# MyProject_2025-03-29.net
KiCad netlist of a schematic drawn in EasyEDA Pro
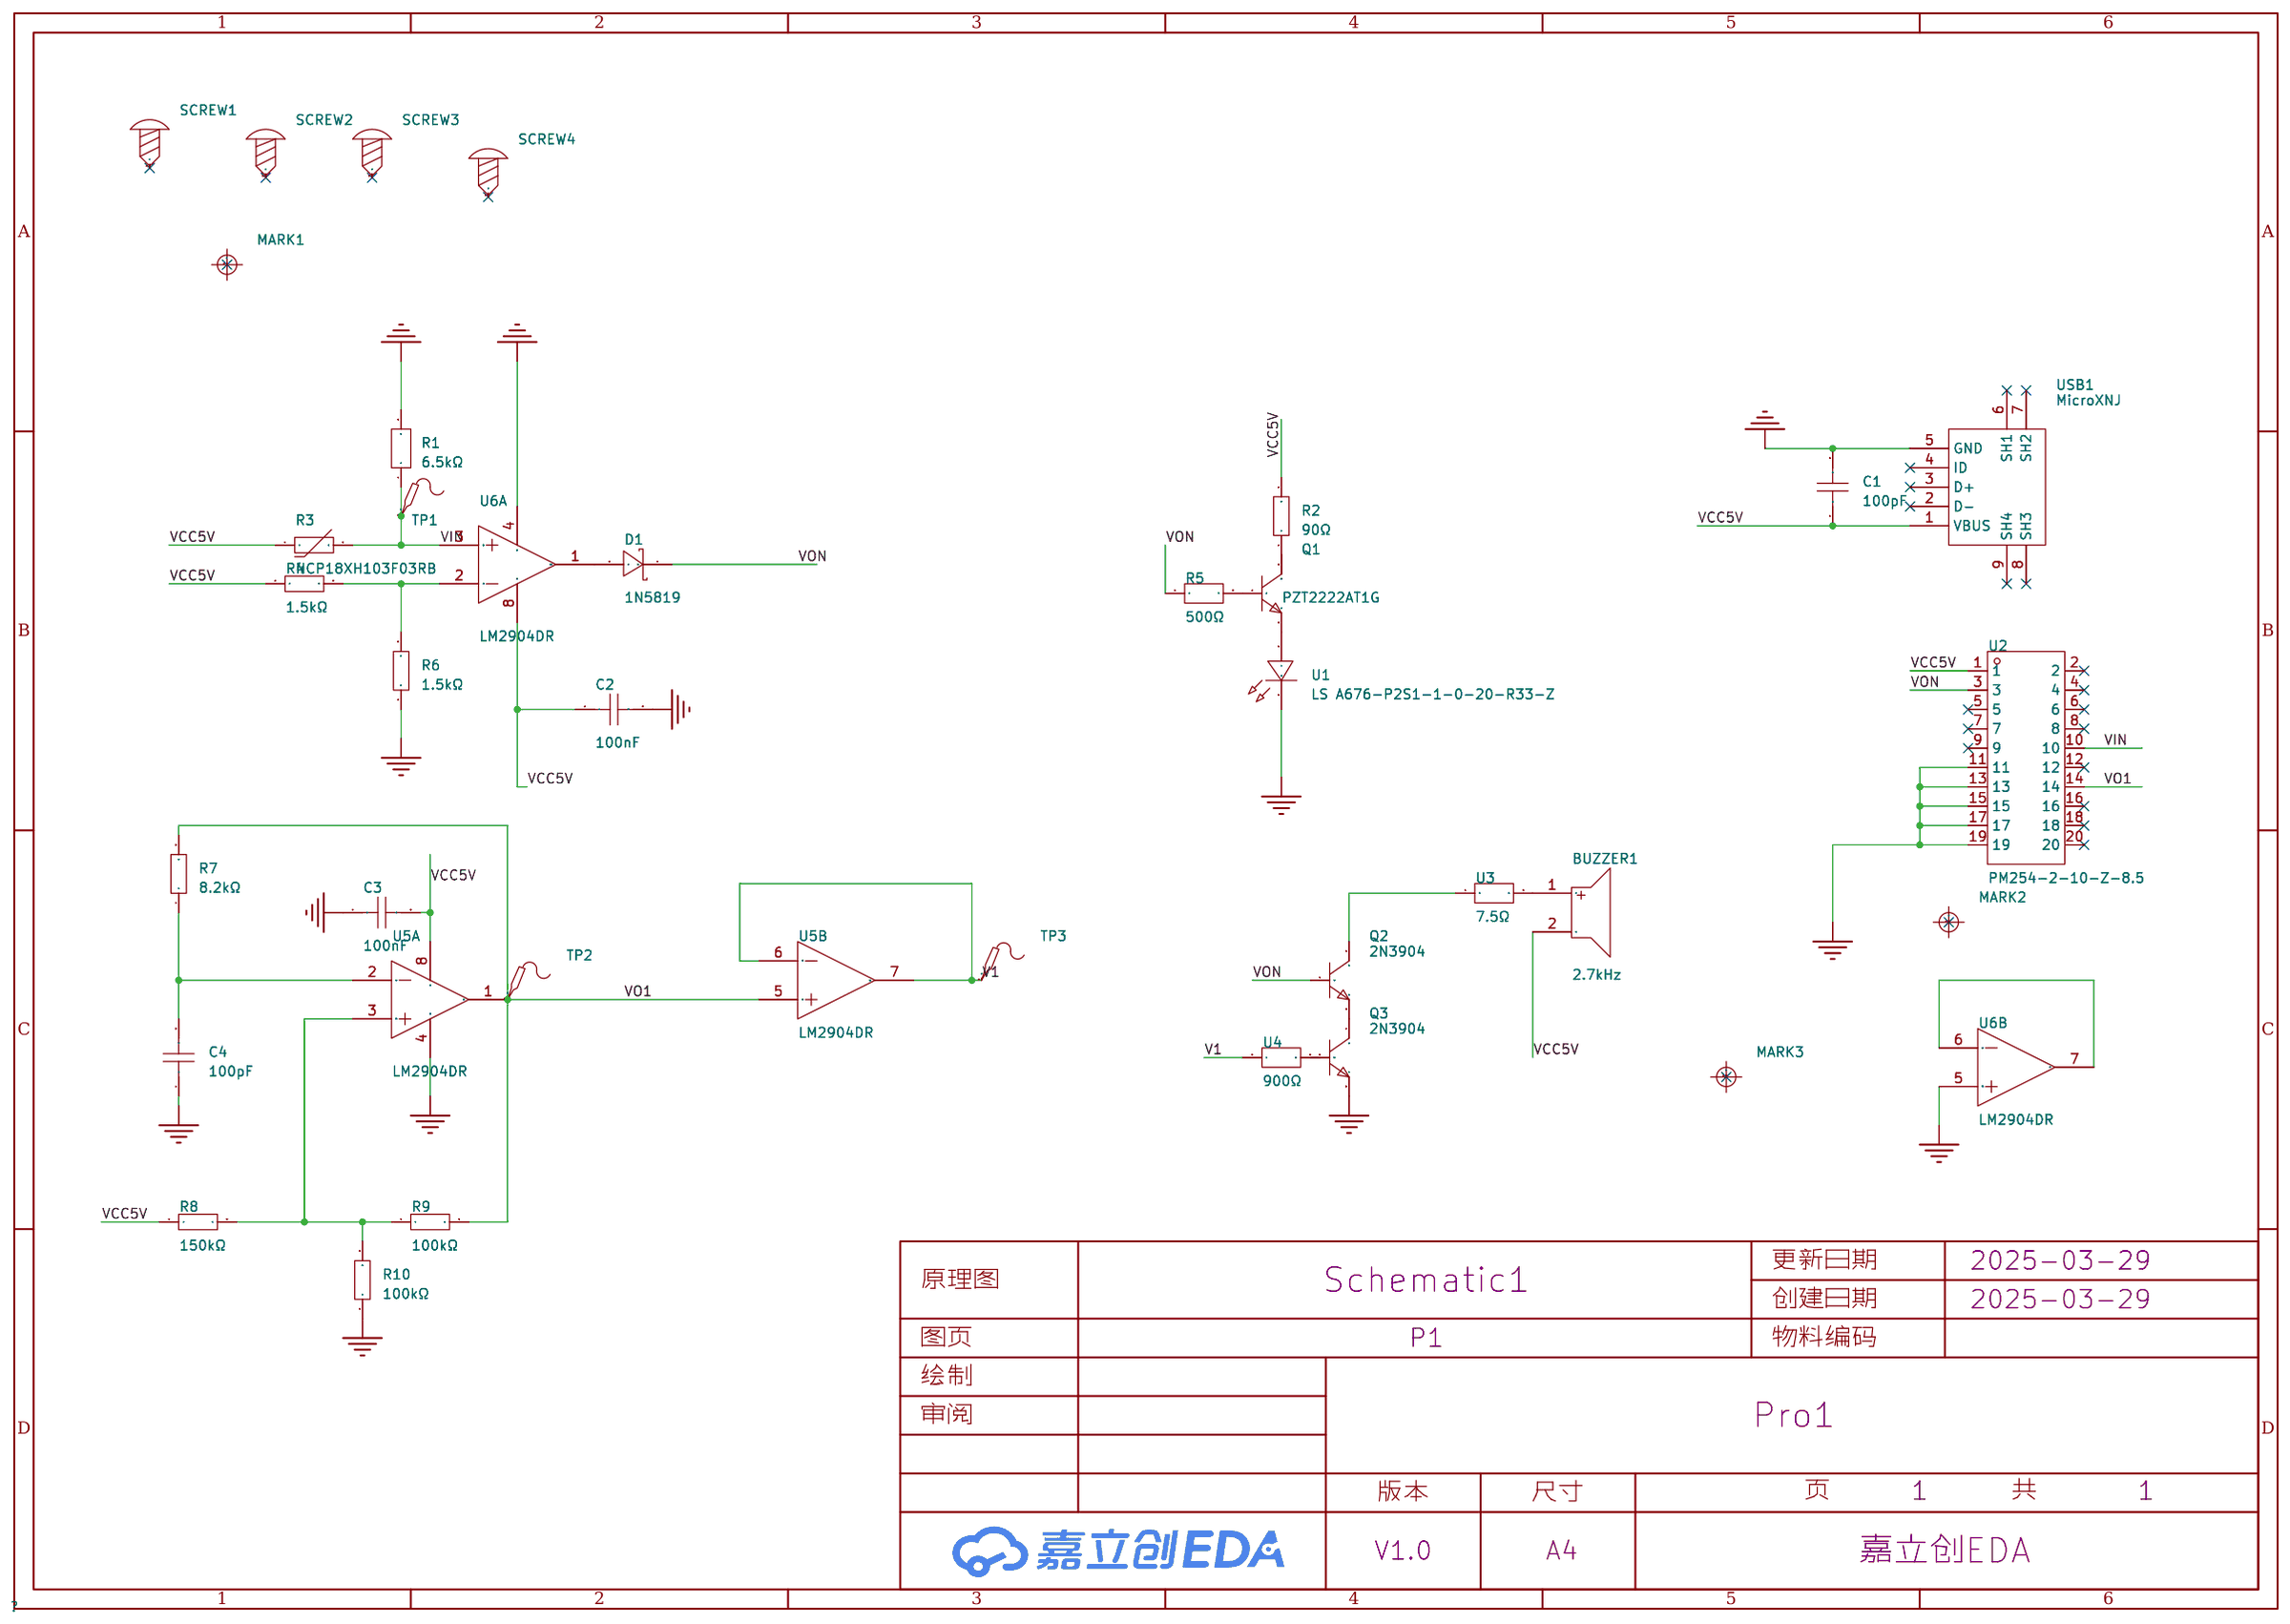
[diagram p0: schematic sheet]

(export (version "E")
  (design (tool "Eeschema 10.0.6"))
  (components
    (comp (ref "BUZZER1")
      (value "2.7kHz")
      (footprint "easyedapro:BUZ-TH_BD9.0-P4.00-D0.6-FD")
      (description "驱动方式:无源(外部驱动);构造类型:电磁式;频率:2.7kHz;声压(SPL):85dB@3V,10cm;")
      (fields (field (name "Manufacturer Part") "QMB-09B-03") (field (name "Manufacturer") "华能"))
      (libsource (lib "easyedapro") (part "QMB-09B-03"))
    )
    (comp (ref "C1")
      (value "100pF")
      (footprint "easyedapro:C0603")
      (description "容值:100pF;精度:±5%;额定电压:50V;材质(温度系数):NP0;")
      (fields
        (field (name "Manufacturer Part") "CC0603JRNPO9BN101")
        (field (name "Manufacturer") "YAGEO(国巨)")
      )
      (libsource (lib "easyedapro") (part "CC0603JRNPO9BN101"))
    )
    (comp (ref "C2")
      (value "100nF")
      (footprint "easyedapro:C0603")
      (description "容值:100nF;精度:±10%;额定电压:50V;材质(温度系数):X7R;")
      (fields
        (field (name "Manufacturer Part") "CC0603KRX7R9BB104")
        (field (name "Manufacturer") "YAGEO(国巨)")
      )
      (libsource (lib "easyedapro") (part "CC0603KRX7R9BB104"))
    )
    (comp (ref "C3")
      (value "100nF")
      (footprint "easyedapro:C0603")
      (description "容值:100nF;精度:±10%;额定电压:50V;材质(温度系数):X7R;")
      (fields
        (field (name "Manufacturer Part") "CC0603KRX7R9BB104")
        (field (name "Manufacturer") "YAGEO(国巨)")
      )
      (libsource (lib "easyedapro") (part "CC0603KRX7R9BB104"))
    )
    (comp (ref "C4")
      (value "100pF")
      (footprint "easyedapro:C0603")
      (description "容值:100pF;精度:±5%;额定电压:50V;材质(温度系数):NP0;")
      (fields
        (field (name "Manufacturer Part") "CC0603JRNPO9BN101")
        (field (name "Manufacturer") "YAGEO(国巨)")
      )
      (libsource (lib "easyedapro") (part "CC0603JRNPO9BN101"))
    )
    (comp (ref "D1")
      (value "1N5819")
      (footprint "easyedapro:SMA_L4.4-W2.6-LS5.0-RD")
      (description "正向压降(Vf):500mV@1A;直流反向耐压(Vr):40V;平均整流电流(Io):1A;")
      (fields (field (name "Manufacturer") "KEXIN(科信)"))
      (libsource (lib "easyedapro") (part "1N5819_C437199"))
    )
    (comp (ref "MARK1")
      (value "~")
      (footprint "easyedapro:Mark-Point-1mm")
      (description "Mark点")
      (libsource (lib "easyedapro") (part "Mark-Point"))
    )
    (comp (ref "MARK2")
      (value "~")
      (footprint "easyedapro:Mark-Point-1mm")
      (description "Mark点")
      (libsource (lib "easyedapro") (part "Mark-Point"))
    )
    (comp (ref "MARK3")
      (value "~")
      (footprint "easyedapro:Mark-Point-1mm")
      (description "Mark点")
      (libsource (lib "easyedapro") (part "Mark-Point"))
    )
    (comp (ref "Q1")
      (value "PZT2222AT1G")
      (footprint "easyedapro:SOT-223_L6.5-W3.5-P2.30-LS7.0-BR")
      (description "晶体管类型:NPN;集电极电流(Ic):600mA;集射极击穿电压(Vceo):40V;功率(Pd):1.5W;直流电流增益(hFE@Ic,Vce):35@150mA,10V;")
      (fields (field (name "Manufacturer") "onsemi(安森美)"))
      (libsource (lib "easyedapro") (part "PZT2222AT1G"))
    )
    (comp (ref "Q2")
      (value "2N3904")
      (footprint "easyedapro:TO-92-3_L4.6-W3.6-P1.27-L_1")
      (description "晶体管类型:NPN;集电极电流(Ic):200mA;集射极击穿电压(Vceo):40V;功率(Pd):625mW;直流电流增益(hFE@Ic,Vce):10@10mA,1V;")
      (fields (field (name "Manufacturer") "JSMSEMI(杰盛微)"))
      (libsource (lib "easyedapro") (part "2N3904_C2874602"))
    )
    (comp (ref "Q3")
      (value "2N3904")
      (footprint "easyedapro:TO-92-3_L4.6-W3.6-P1.27-L_1")
      (description "晶体管类型:NPN;集电极电流(Ic):200mA;集射极击穿电压(Vceo):40V;功率(Pd):625mW;直流电流增益(hFE@Ic,Vce):10@10mA,1V;")
      (fields (field (name "Manufacturer") "JSMSEMI(杰盛微)"))
      (libsource (lib "easyedapro") (part "2N3904_C2874602"))
    )
    (comp (ref "R1")
      (value "6.5kΩ")
      (footprint "easyedapro:R0603")
      (description "电阻类型:薄膜电阻;阻值:6.5kΩ;精度:±0.1%;功率:100mW;最大工作电压:75V;温度系数:±25ppm/°C;")
      (fields
        (field (name "Manufacturer Part") "MCT06030D6501BP100")
        (field (name "Manufacturer") "VISHAY(威世)")
      )
      (libsource (lib "easyedapro") (part "MCT06030D6501BP100"))
    )
    (comp (ref "R2")
      (value "90Ω")
      (footprint "easyedapro:R0805")
      (description "电阻类型:厚膜电阻;阻值:90Ω;精度:±1%;功率:125mW;最大工作电压:150V;温度系数:±100ppm/°C;")
      (fields (field (name "Manufacturer Part") "RS-05K90R0FT") (field (name "Manufacturer") "FH(风华)"))
      (libsource (lib "easyedapro") (part "RS-05K90R0FT"))
    )
    (comp (ref "R3")
      (value "NCP18XH103F03RB")
      (footprint "easyedapro:R0603")
      (description "阻值(25°C):10kΩ;B值(25°C/50°C):3380K;电阻精度:±1%;功率:100mW;B值精度:±1%;最大稳态电流(25°C):310uA;")
      (fields (field (name "Manufacturer") "muRata(村田)"))
      (libsource (lib "easyedapro") (part "NCP18XH103F03RB"))
    )
    (comp (ref "R4")
      (value "1.5kΩ")
      (footprint "easyedapro:R0603")
      (description "电阻类型:厚膜电阻;阻值:1.5kΩ;精度:±1%;功率:100mW;最大工作电压:75V;温度系数:±100ppm/°C;")
      (fields
        (field (name "Manufacturer Part") "0603WAF1501T5E")
        (field (name "Manufacturer") "UNI-ROYAL(厚声)")
      )
      (libsource (lib "easyedapro") (part "0603WAF1501T5E"))
    )
    (comp (ref "R5")
      (value "500Ω")
      (footprint "easyedapro:R0805")
      (description "电阻类型:薄膜电阻;阻值:500Ω;精度:±1%;功率:125mW;最大工作电压:150V;温度系数:±25ppm/°C;")
      (fields (field (name "Manufacturer Part") "ARG05FTC5000") (field (name "Manufacturer") "Viking(光颉)"))
      (libsource (lib "easyedapro") (part "ARG05FTC5000"))
    )
    (comp (ref "R6")
      (value "1.5kΩ")
      (footprint "easyedapro:R0603")
      (description "电阻类型:厚膜电阻;阻值:1.5kΩ;精度:±1%;功率:100mW;最大工作电压:75V;温度系数:±100ppm/°C;")
      (fields
        (field (name "Manufacturer Part") "0603WAF1501T5E")
        (field (name "Manufacturer") "UNI-ROYAL(厚声)")
      )
      (libsource (lib "easyedapro") (part "0603WAF1501T5E"))
    )
    (comp (ref "R7")
      (value "8.2kΩ")
      (footprint "easyedapro:R0603")
      (description "电阻类型:厚膜电阻;阻值:8.2kΩ;精度:±1%;功率:100mW;最大工作电压:75V;温度系数:±100ppm/°C;")
      (fields
        (field (name "Manufacturer Part") "0603WAF8201T5E")
        (field (name "Manufacturer") "UNI-ROYAL(厚声)")
      )
      (libsource (lib "easyedapro") (part "0603WAF8201T5E"))
    )
    (comp (ref "R8")
      (value "150kΩ")
      (footprint "easyedapro:R0603")
      (description "电阻类型:厚膜电阻;阻值:150kΩ;精度:±1%;功率:100mW;最大工作电压:75V;温度系数:±100ppm/°C;")
      (fields
        (field (name "Manufacturer Part") "0603WAF1503T5E")
        (field (name "Manufacturer") "UNI-ROYAL(厚声)")
      )
      (libsource (lib "easyedapro") (part "0603WAF1503T5E"))
    )
    (comp (ref "R9")
      (value "100kΩ")
      (footprint "easyedapro:R0603")
      (description "电阻类型:厚膜电阻;阻值:100kΩ;精度:±1%;功率:100mW;最大工作电压:75V;温度系数:±100ppm/°C;")
      (fields
        (field (name "Manufacturer Part") "0603WAF1003T5E")
        (field (name "Manufacturer") "UNI-ROYAL(厚声)")
      )
      (libsource (lib "easyedapro") (part "0603WAF1003T5E"))
    )
    (comp (ref "R10")
      (value "100kΩ")
      (footprint "easyedapro:R0603")
      (description "电阻类型:厚膜电阻;阻值:100kΩ;精度:±1%;功率:100mW;最大工作电压:75V;温度系数:±100ppm/°C;")
      (fields
        (field (name "Manufacturer Part") "0603WAF1003T5E")
        (field (name "Manufacturer") "UNI-ROYAL(厚声)")
      )
      (libsource (lib "easyedapro") (part "0603WAF1003T5E"))
    )
    (comp (ref "SCREW1")
      (value "~")
      (footprint "easyedapro:M3螺丝")
      (libsource (lib "easyedapro") (part "螺丝孔"))
    )
    (comp (ref "SCREW2")
      (value "~")
      (footprint "easyedapro:M3螺丝")
      (libsource (lib "easyedapro") (part "螺丝孔"))
    )
    (comp (ref "SCREW3")
      (value "~")
      (footprint "easyedapro:M3螺丝")
      (libsource (lib "easyedapro") (part "螺丝孔"))
    )
    (comp (ref "SCREW4")
      (value "~")
      (footprint "easyedapro:M3螺丝")
      (libsource (lib "easyedapro") (part "螺丝孔"))
    )
    (comp (ref "TP1")
      (value "~")
      (footprint "easyedapro:Test-Point-0.5mm")
      (description "Test Point 测试点")
      (libsource (lib "easyedapro") (part "Test-Point"))
    )
    (comp (ref "TP2")
      (value "~")
      (footprint "easyedapro:Test-Point-0.5mm")
      (description "Test Point 测试点")
      (libsource (lib "easyedapro") (part "Test-Point"))
    )
    (comp (ref "TP3")
      (value "~")
      (footprint "easyedapro:Test-Point-0.5mm")
      (description "Test Point 测试点")
      (libsource (lib "easyedapro") (part "Test-Point"))
    )
    (comp (ref "U1")
      (value "LS A676-P2S1-1-0-20-R33-Z")
      (footprint "easyedapro:LED-SMD_L4.0-W3.6-P2.54-RD")
      (fields (field (name "Manufacturer") "OSRAM(欧司朗)"))
      (libsource (lib "easyedapro") (part "LS A676-P2S1-1-0-20-R33-Z"))
    )
    (comp (ref "U2")
      (value "PM254-2-10-Z-8.5")
      (footprint "easyedapro:HDR-TH_20P-P2.54-V-F-R2-C10-S2.54")
      (fields (field (name "Manufacturer") "HCTL(华灿天禄)"))
      (libsource (lib "easyedapro") (part "PM254-2-10-Z-8.5"))
    )
    (comp (ref "U3")
      (value "7.5Ω")
      (footprint "easyedapro:R1206")
      (description "电阻类型:厚膜电阻;阻值:7.5Ω;精度:±1%;功率:250mW;最大工作电压:200V;温度系数:±200ppm/°C;")
      (fields (field (name "Manufacturer Part") "FRC1206F7R50TS") (field (name "Manufacturer") "FOJAN(富捷)"))
      (libsource (lib "easyedapro") (part "FRC1206F7R50TS"))
    )
    (comp (ref "U4")
      (value "900Ω")
      (footprint "easyedapro:R0805")
      (description "电阻类型:薄膜电阻;阻值:900Ω;精度:±0.1%;功率:125mW;最大工作电压:150V;温度系数:±25ppm/°C;")
      (fields (field (name "Manufacturer Part") "ARG05BTC9000N") (field (name "Manufacturer") "Viking(光颉)"))
      (libsource (lib "easyedapro") (part "ARG05BTC9000N"))
    )
    (comp (ref "U5")
      (value "LM2904DR")
      (footprint "easyedapro:SOIC-8_L4.9-W3.9-P1.27-LS6.0-BL")
      (description "放大器数:双路;增益带宽积(GBP):700kHz;输入偏置电流(Ib):20nA;压摆率(SR):0.3V/us;带宽(-3db):-;")
      (fields (field (name "Manufacturer") "TI(德州仪器)"))
      (libsource (lib "easyedapro") (part "LM2904DR"))
    )
    (comp (ref "U6")
      (value "LM2904DR")
      (footprint "easyedapro:SOIC-8_L4.9-W3.9-P1.27-LS6.0-BL")
      (description "放大器数:双路;增益带宽积(GBP):700kHz;输入偏置电流(Ib):20nA;压摆率(SR):0.3V/us;带宽(-3db):-;")
      (fields (field (name "Manufacturer") "TI(德州仪器)"))
      (libsource (lib "easyedapro") (part "LM2904DR"))
    )
    (comp (ref "USB1")
      (value "MicroXNJ")
      (footprint "easyedapro:MICRO-USB-SMD_MICROXNJ")
      (description "连接器类型:Micro-B;标准:USB 2.0;公母:母;安装方式:卧贴;触点数量:5P;端口数量:1;额定电流 - 电源:1A;工作温度范围:-20°C~+85°C;")
      (fields (field (name "Manufacturer") "SHOU HAN(首韩)"))
      (libsource (lib "easyedapro") (part "MICROXNJ"))
    )
  )
  (nets
    (net (code "1") (name "/V1") (class "Default")
      (node (ref "TP3") (pin "1") (pinfunction "1_1") (pintype "input"))
      (node (ref "U4") (pin "1") (pinfunction "1_1") (pintype "unspecified"))
      (node (ref "U5") (pin "6") (pinfunction "2IN-_6") (pintype "unspecified"))
      (node (ref "U5") (pin "7") (pinfunction "2OUT_7") (pintype "output"))
    )
    (net (code "2") (name "/VCC5V") (class "Default")
      (node (ref "BUZZER1") (pin "2") (pinfunction "2_2") (pintype "unspecified"))
      (node (ref "C1") (pin "1") (pinfunction "1_1") (pintype "unspecified"))
      (node (ref "C2") (pin "1") (pinfunction "1_1") (pintype "unspecified"))
      (node (ref "C3") (pin "2") (pinfunction "2_2") (pintype "unspecified"))
      (node (ref "R2") (pin "2") (pinfunction "2_2") (pintype "unspecified"))
      (node (ref "R3") (pin "1") (pinfunction "1_1") (pintype "input"))
      (node (ref "R4") (pin "1") (pinfunction "1_1") (pintype "input"))
      (node (ref "R8") (pin "1") (pinfunction "1_1") (pintype "input"))
      (node (ref "U2") (pin "1") (pinfunction "1_1") (pintype "unspecified"))
      (node (ref "U5") (pin "8") (pinfunction "VCC_8") (pintype "unspecified"))
      (node (ref "U6") (pin "8") (pinfunction "VCC_8") (pintype "unspecified"))
      (node (ref "USB1") (pin "1") (pinfunction "VBUS_1") (pintype "unspecified"))
    )
    (net (code "3") (name "/VIN") (class "Default")
      (node (ref "R1") (pin "1") (pinfunction "1_1") (pintype "unspecified"))
      (node (ref "R3") (pin "2") (pinfunction "2_2") (pintype "input"))
      (node (ref "TP1") (pin "1") (pinfunction "1_1") (pintype "input"))
      (node (ref "U2") (pin "10") (pinfunction "10_10") (pintype "unspecified"))
      (node (ref "U6") (pin "3") (pinfunction "1IN+_3") (pintype "unspecified"))
    )
    (net (code "4") (name "/VO1") (class "Default")
      (node (ref "R7") (pin "2") (pinfunction "2_2") (pintype "input"))
      (node (ref "R9") (pin "2") (pinfunction "2_2") (pintype "input"))
      (node (ref "TP2") (pin "1") (pinfunction "1_1") (pintype "input"))
      (node (ref "U2") (pin "14") (pinfunction "14_14") (pintype "unspecified"))
      (node (ref "U5") (pin "1") (pinfunction "1OUT_1") (pintype "output"))
      (node (ref "U5") (pin "5") (pinfunction "2IN+_5") (pintype "unspecified"))
    )
    (net (code "5") (name "/VON") (class "Default")
      (node (ref "D1") (pin "1") (pinfunction "C_1") (pintype "unspecified"))
      (node (ref "Q2") (pin "2") (pinfunction "B_2") (pintype "unspecified"))
      (node (ref "R5") (pin "1") (pinfunction "1_1") (pintype "unspecified"))
      (node (ref "U2") (pin "3") (pinfunction "3_3") (pintype "unspecified"))
    )
    (net (code "6") (name "GND") (class "Default")
      (node (ref "C1") (pin "2") (pinfunction "2_2") (pintype "unspecified"))
      (node (ref "C2") (pin "2") (pinfunction "2_2") (pintype "unspecified"))
      (node (ref "C3") (pin "1") (pinfunction "1_1") (pintype "unspecified"))
      (node (ref "C4") (pin "1") (pinfunction "1_1") (pintype "unspecified"))
      (node (ref "Q3") (pin "3") (pinfunction "E_3") (pintype "unspecified"))
      (node (ref "R1") (pin "2") (pinfunction "2_2") (pintype "unspecified"))
      (node (ref "R10") (pin "1") (pinfunction "1_1") (pintype "input"))
      (node (ref "R6") (pin "1") (pinfunction "1_1") (pintype "input"))
      (node (ref "U1") (pin "1") (pinfunction "C_1") (pintype "unspecified"))
      (node (ref "U2") (pin "11") (pinfunction "11_11") (pintype "unspecified"))
      (node (ref "U2") (pin "13") (pinfunction "13_13") (pintype "unspecified"))
      (node (ref "U2") (pin "15") (pinfunction "15_15") (pintype "unspecified"))
      (node (ref "U2") (pin "17") (pinfunction "17_17") (pintype "unspecified"))
      (node (ref "U2") (pin "19") (pinfunction "19_19") (pintype "unspecified"))
      (node (ref "U5") (pin "4") (pinfunction "GND_4") (pintype "unspecified"))
      (node (ref "U6") (pin "4") (pinfunction "GND_4") (pintype "unspecified"))
      (node (ref "U6") (pin "5") (pinfunction "2IN+_5") (pintype "unspecified"))
      (node (ref "USB1") (pin "5") (pinfunction "GND_5") (pintype "unspecified"))
    )
    (net (code "7") (name "Net-(BUZZER1-Pad1)") (class "Default")
      (node (ref "BUZZER1") (pin "1") (pinfunction "1_1") (pintype "unspecified"))
      (node (ref "U3") (pin "2") (pinfunction "2_2") (pintype "unspecified"))
    )
    (net (code "8") (name "Net-(D1-A)") (class "Default")
      (node (ref "D1") (pin "2") (pinfunction "A_2") (pintype "unspecified"))
      (node (ref "U6") (pin "1") (pinfunction "1OUT_1") (pintype "output"))
    )
    (net (code "9") (name "Net-(Q1-B)") (class "Default")
      (node (ref "Q1") (pin "1") (pinfunction "B_1") (pintype "unspecified"))
      (node (ref "R5") (pin "2") (pinfunction "2_2") (pintype "unspecified"))
    )
    (net (code "10") (name "Net-(Q1-C-Pad2)") (class "Default")
      (node (ref "Q1") (pin "2") (pinfunction "C_2") (pintype "unspecified"))
      (node (ref "Q1") (pin "4") (pinfunction "C_4") (pintype "unspecified"))
      (node (ref "R2") (pin "1") (pinfunction "1_1") (pintype "unspecified"))
    )
    (net (code "11") (name "Net-(Q1-E)") (class "Default")
      (node (ref "Q1") (pin "3") (pinfunction "E_3") (pintype "unspecified"))
      (node (ref "U1") (pin "2") (pinfunction "A_2") (pintype "unspecified"))
    )
    (net (code "12") (name "Net-(Q2-C)") (class "Default")
      (node (ref "Q2") (pin "1") (pinfunction "C_1") (pintype "unspecified"))
      (node (ref "U3") (pin "1") (pinfunction "1_1") (pintype "unspecified"))
    )
    (net (code "13") (name "Net-(Q2-E)") (class "Default")
      (node (ref "Q2") (pin "3") (pinfunction "E_3") (pintype "unspecified"))
      (node (ref "Q3") (pin "1") (pinfunction "C_1") (pintype "unspecified"))
    )
    (net (code "14") (name "Net-(Q3-B)") (class "Default")
      (node (ref "Q3") (pin "2") (pinfunction "B_2") (pintype "unspecified"))
      (node (ref "U4") (pin "2") (pinfunction "2_2") (pintype "unspecified"))
    )
    (net (code "15") (name "Net-(U5A-1IN+)") (class "Default")
      (node (ref "R10") (pin "2") (pinfunction "2_2") (pintype "input"))
      (node (ref "R8") (pin "2") (pinfunction "2_2") (pintype "input"))
      (node (ref "R9") (pin "1") (pinfunction "1_1") (pintype "input"))
      (node (ref "U5") (pin "3") (pinfunction "1IN+_3") (pintype "unspecified"))
    )
    (net (code "16") (name "Net-(U5A-1IN-)") (class "Default")
      (node (ref "C4") (pin "2") (pinfunction "2_2") (pintype "unspecified"))
      (node (ref "R7") (pin "1") (pinfunction "1_1") (pintype "input"))
      (node (ref "U5") (pin "2") (pinfunction "1IN-_2") (pintype "unspecified"))
    )
    (net (code "17") (name "Net-(U6A-1IN-)") (class "Default")
      (node (ref "R4") (pin "2") (pinfunction "2_2") (pintype "input"))
      (node (ref "R6") (pin "2") (pinfunction "2_2") (pintype "input"))
      (node (ref "U6") (pin "2") (pinfunction "1IN-_2") (pintype "unspecified"))
    )
    (net (code "18") (name "Net-(U6B-2IN-)") (class "Default")
      (node (ref "U6") (pin "6") (pinfunction "2IN-_6") (pintype "unspecified"))
      (node (ref "U6") (pin "7") (pinfunction "2OUT_7") (pintype "output"))
    )
    (net (code "19") (name "unconnected-(MARK1-Pad1)") (class "Default")
      (node (ref "MARK1") (pin "1") (pinfunction "1_1") (pintype "input+no_connect"))
    )
    (net (code "20") (name "unconnected-(MARK2-Pad1)") (class "Default")
      (node (ref "MARK2") (pin "1") (pinfunction "1_1") (pintype "input+no_connect"))
    )
    (net (code "21") (name "unconnected-(MARK3-Pad1)") (class "Default")
      (node (ref "MARK3") (pin "1") (pinfunction "1_1") (pintype "input+no_connect"))
    )
    (net (code "22") (name "unconnected-(SCREW1-Pad1)") (class "Default")
      (node (ref "SCREW1") (pin "1") (pinfunction "1_1") (pintype "input+no_connect"))
    )
    (net (code "23") (name "unconnected-(SCREW2-Pad1)") (class "Default")
      (node (ref "SCREW2") (pin "1") (pinfunction "1_1") (pintype "input+no_connect"))
    )
    (net (code "24") (name "unconnected-(SCREW3-Pad1)") (class "Default")
      (node (ref "SCREW3") (pin "1") (pinfunction "1_1") (pintype "input+no_connect"))
    )
    (net (code "25") (name "unconnected-(SCREW4-Pad1)") (class "Default")
      (node (ref "SCREW4") (pin "1") (pinfunction "1_1") (pintype "input+no_connect"))
    )
    (net (code "26") (name "unconnected-(U2-Pad2)") (class "Default")
      (node (ref "U2") (pin "2") (pinfunction "2_2") (pintype "unspecified+no_connect"))
    )
    (net (code "27") (name "unconnected-(U2-Pad4)") (class "Default")
      (node (ref "U2") (pin "4") (pinfunction "4_4") (pintype "unspecified+no_connect"))
    )
    (net (code "28") (name "unconnected-(U2-Pad5)") (class "Default")
      (node (ref "U2") (pin "5") (pinfunction "5_5") (pintype "unspecified+no_connect"))
    )
    (net (code "29") (name "unconnected-(U2-Pad6)") (class "Default")
      (node (ref "U2") (pin "6") (pinfunction "6_6") (pintype "unspecified+no_connect"))
    )
    (net (code "30") (name "unconnected-(U2-Pad7)") (class "Default")
      (node (ref "U2") (pin "7") (pinfunction "7_7") (pintype "unspecified+no_connect"))
    )
    (net (code "31") (name "unconnected-(U2-Pad8)") (class "Default")
      (node (ref "U2") (pin "8") (pinfunction "8_8") (pintype "unspecified+no_connect"))
    )
    (net (code "32") (name "unconnected-(U2-Pad9)") (class "Default")
      (node (ref "U2") (pin "9") (pinfunction "9_9") (pintype "unspecified+no_connect"))
    )
    (net (code "33") (name "unconnected-(U2-Pad12)") (class "Default")
      (node (ref "U2") (pin "12") (pinfunction "12_12") (pintype "unspecified+no_connect"))
    )
    (net (code "34") (name "unconnected-(U2-Pad16)") (class "Default")
      (node (ref "U2") (pin "16") (pinfunction "16_16") (pintype "unspecified+no_connect"))
    )
    (net (code "35") (name "unconnected-(U2-Pad18)") (class "Default")
      (node (ref "U2") (pin "18") (pinfunction "18_18") (pintype "unspecified+no_connect"))
    )
    (net (code "36") (name "unconnected-(U2-Pad20)") (class "Default")
      (node (ref "U2") (pin "20") (pinfunction "20_20") (pintype "unspecified+no_connect"))
    )
    (net (code "37") (name "unconnected-(USB1-D+-Pad3)") (class "Default")
      (node (ref "USB1") (pin "3") (pinfunction "D+_3") (pintype "unspecified+no_connect"))
    )
    (net (code "38") (name "unconnected-(USB1-D--Pad2)") (class "Default")
      (node (ref "USB1") (pin "2") (pinfunction "D-_2") (pintype "unspecified+no_connect"))
    )
    (net (code "39") (name "unconnected-(USB1-ID-Pad4)") (class "Default")
      (node (ref "USB1") (pin "4") (pinfunction "ID_4") (pintype "unspecified+no_connect"))
    )
    (net (code "40") (name "unconnected-(USB1-SH1-Pad6)") (class "Default")
      (node (ref "USB1") (pin "6") (pinfunction "SH1_6") (pintype "unspecified+no_connect"))
    )
    (net (code "41") (name "unconnected-(USB1-SH2-Pad7)") (class "Default")
      (node (ref "USB1") (pin "7") (pinfunction "SH2_7") (pintype "unspecified+no_connect"))
    )
    (net (code "42") (name "unconnected-(USB1-SH3-Pad8)") (class "Default")
      (node (ref "USB1") (pin "8") (pinfunction "SH3_8") (pintype "unspecified+no_connect"))
    )
    (net (code "43") (name "unconnected-(USB1-SH4-Pad9)") (class "Default")
      (node (ref "USB1") (pin "9") (pinfunction "SH4_9") (pintype "unspecified+no_connect"))
    )
  )
)
